# -_-.net
KiCad netlist of a schematic drawn in Altium Designer
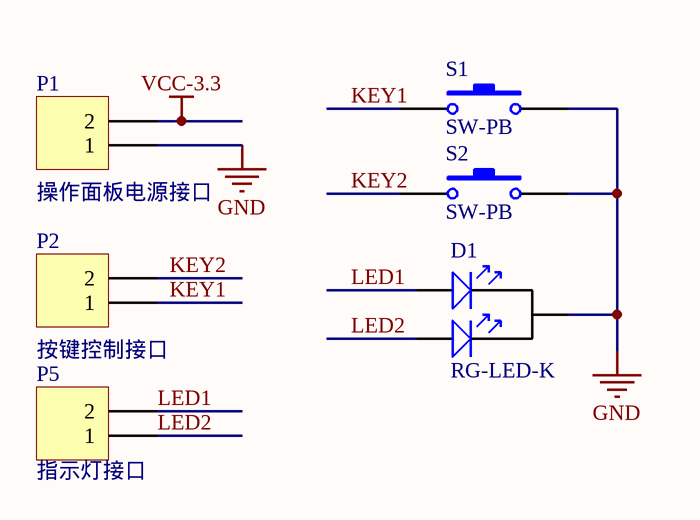
[diagram p0: 智能家居-开关-按键板.SchDoc]

(export (version "E")
  (design (tool "Eeschema 10.0.6"))
  (components
    (comp (ref "D1")
      (value "RG-LED-K")
      (footprint "RG-LED")
      (libsource (lib "ESP8266V1.2") (part "RG-LED-K"))
    )
    (comp (ref "P1")
      (value "操作面板电源接口")
      (footprint "DG1282")
      (description "Header, 2-Pin, Right Angle")
      (fields (field (name "PUBLISHER") "Altium Limited"))
      (libsource (lib "Miscellaneous Connectors") (part "Header 2H"))
    )
    (comp (ref "P2")
      (value "按键控制接口")
      (footprint "DG1282")
      (description "Header, 2-Pin, Right Angle")
      (fields (field (name "PUBLISHER") "Altium Limited"))
      (libsource (lib "Miscellaneous Connectors") (part "Header 2H"))
    )
    (comp (ref "P5")
      (value "指示灯接口")
      (footprint "DG1282")
      (description "Header, 2-Pin, Right Angle")
      (fields (field (name "PUBLISHER") "Altium Limited"))
      (libsource (lib "Miscellaneous Connectors") (part "Header 2H"))
    )
    (comp (ref "S1")
      (value "SW-PB")
      (footprint "KEY_M")
      (description "Switch")
      (fields (field (name "PUBLISHER") "Altium Limited"))
      (libsource (lib "Miscellaneous Devices") (part "SW-PB"))
    )
    (comp (ref "S2")
      (value "SW-PB")
      (footprint "KEY_M")
      (description "Switch")
      (fields (field (name "PUBLISHER") "Altium Limited"))
      (libsource (lib "Miscellaneous Devices") (part "SW-PB"))
    )
  )
  (nets
    (net (code "1") (name "/KEY1") (class "Default")
      (node (ref "P2") (pin "1") (pinfunction "1_1") (pintype "passive"))
      (node (ref "S1") (pin "1") (pinfunction "1_1") (pintype "passive"))
    )
    (net (code "2") (name "/KEY2") (class "Default")
      (node (ref "P2") (pin "2") (pinfunction "2_2") (pintype "passive"))
      (node (ref "S2") (pin "1") (pinfunction "1_1") (pintype "passive"))
    )
    (net (code "3") (name "/LED1") (class "Default")
      (node (ref "D1") (pin "1") (pinfunction "R_1") (pintype "passive"))
      (node (ref "P5") (pin "2") (pinfunction "2_2") (pintype "passive"))
    )
    (net (code "4") (name "/LED2") (class "Default")
      (node (ref "D1") (pin "3") (pinfunction "G_3") (pintype "passive"))
      (node (ref "P5") (pin "1") (pinfunction "1_1") (pintype "passive"))
    )
    (net (code "5") (name "GND") (class "Default")
      (node (ref "D1") (pin "2") (pinfunction "GND_2") (pintype "passive"))
      (node (ref "P1") (pin "1") (pinfunction "1_1") (pintype "passive"))
      (node (ref "S1") (pin "2") (pinfunction "2_2") (pintype "passive"))
      (node (ref "S2") (pin "2") (pinfunction "2_2") (pintype "passive"))
    )
    (net (code "6") (name "VCC-3.3") (class "Default")
      (node (ref "P1") (pin "2") (pinfunction "2_2") (pintype "passive"))
    )
  )
)
